# BaromBoard.net
KiCad netlist of a schematic drawn in EAGLE
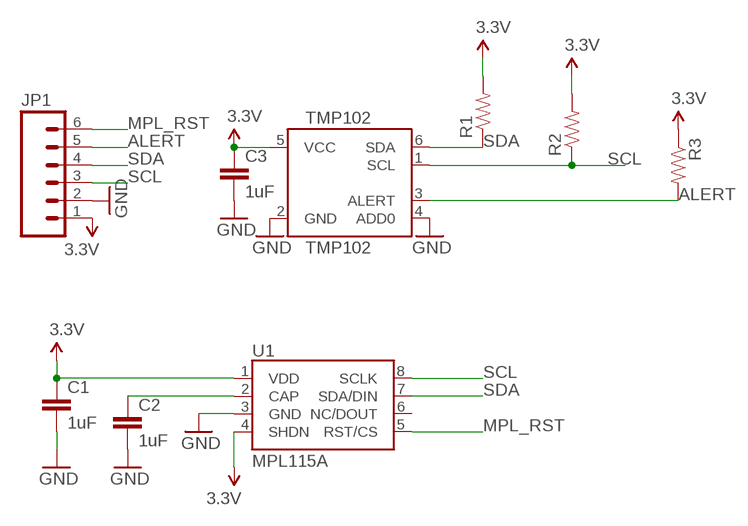
[diagram p0: schematic, sheet 1]

(export (version "E")
  (design (tool "Eeschema 10.0.6"))
  (components
    (comp (ref "C1")
      (value "1uF")
      (footprint "eagle-import:0603-CAP")
      (libsource (lib "eagle-import") (part "CAP0603-CAP"))
    )
    (comp (ref "C2")
      (value "1uF")
      (footprint "eagle-import:0603-CAP")
      (libsource (lib "eagle-import") (part "CAP0603-CAP"))
    )
    (comp (ref "C3")
      (value "1uF")
      (footprint "eagle-import:0603-CAP")
      (libsource (lib "eagle-import") (part "CAP0603-CAP"))
    )
    (comp (ref "JP1")
      (value "M06SIP")
      (footprint "eagle-import:1X06")
      (libsource (lib "eagle-import") (part "M06SIP"))
    )
    (comp (ref "R1")
      (value "RESISTOR0603-RES")
      (footprint "eagle-import:0603-RES")
      (libsource (lib "eagle-import") (part "RESISTOR0603-RES"))
    )
    (comp (ref "R2")
      (value "RESISTOR0603-RES")
      (footprint "eagle-import:0603-RES")
      (libsource (lib "eagle-import") (part "RESISTOR0603-RES"))
    )
    (comp (ref "R3")
      (value "RESISTOR0603-RES")
      (footprint "eagle-import:0603-RES")
      (libsource (lib "eagle-import") (part "RESISTOR0603-RES"))
    )
    (comp (ref "TMP102")
      (value "TMP102")
      (footprint "eagle-import:SOT563")
      (libsource (lib "eagle-import") (part "TMP102"))
    )
    (comp (ref "U1")
      (value "MPL115A")
      (footprint "eagle-import:LGA8")
      (libsource (lib "eagle-import") (part "MPL115A"))
    )
  )
  (nets
    (net (code "1") (name "/ALERT") (class "Default")
      (node (ref "JP1") (pin "5") (pinfunction "5_5") (pintype "passive"))
      (node (ref "R3") (pin "2") (pinfunction "2_2") (pintype "passive"))
      (node (ref "TMP102") (pin "3") (pinfunction "ALERT_3") (pintype "bidirectional"))
    )
    (net (code "2") (name "/MPL_RST") (class "Default")
      (node (ref "JP1") (pin "6") (pinfunction "6_6") (pintype "passive"))
      (node (ref "U1") (pin "5") (pinfunction "RST/CS_5") (pintype "bidirectional"))
    )
    (net (code "3") (name "/SCL") (class "Default")
      (node (ref "JP1") (pin "3") (pinfunction "3_3") (pintype "passive"))
      (node (ref "R2") (pin "1") (pinfunction "1_1") (pintype "passive"))
      (node (ref "TMP102") (pin "1") (pinfunction "SCL_1") (pintype "bidirectional"))
      (node (ref "U1") (pin "8") (pinfunction "SCLK_8") (pintype "bidirectional"))
    )
    (net (code "4") (name "/SDA") (class "Default")
      (node (ref "JP1") (pin "4") (pinfunction "4_4") (pintype "passive"))
      (node (ref "R1") (pin "1") (pinfunction "1_1") (pintype "passive"))
      (node (ref "TMP102") (pin "6") (pinfunction "SDA_6") (pintype "bidirectional"))
      (node (ref "U1") (pin "7") (pinfunction "SDA/DIN_7") (pintype "bidirectional"))
    )
    (net (code "5") (name "3.3V") (class "Default")
      (node (ref "C1") (pin "1") (pinfunction "1_1") (pintype "passive"))
      (node (ref "C3") (pin "1") (pinfunction "1_1") (pintype "passive"))
      (node (ref "JP1") (pin "1") (pinfunction "1_1") (pintype "passive"))
      (node (ref "R1") (pin "2") (pinfunction "2_2") (pintype "passive"))
      (node (ref "R2") (pin "2") (pinfunction "2_2") (pintype "passive"))
      (node (ref "R3") (pin "1") (pinfunction "1_1") (pintype "passive"))
      (node (ref "TMP102") (pin "5") (pinfunction "VCC_5") (pintype "bidirectional"))
      (node (ref "U1") (pin "1") (pinfunction "VDD_1") (pintype "bidirectional"))
      (node (ref "U1") (pin "4") (pinfunction "SHDN_4") (pintype "bidirectional"))
    )
    (net (code "6") (name "GND") (class "Default")
      (node (ref "C1") (pin "2") (pinfunction "2_2") (pintype "passive"))
      (node (ref "C2") (pin "2") (pinfunction "2_2") (pintype "passive"))
      (node (ref "C3") (pin "2") (pinfunction "2_2") (pintype "passive"))
      (node (ref "JP1") (pin "2") (pinfunction "2_2") (pintype "passive"))
      (node (ref "TMP102") (pin "2") (pinfunction "GND_2") (pintype "bidirectional"))
      (node (ref "TMP102") (pin "4") (pinfunction "ADD0_4") (pintype "bidirectional"))
      (node (ref "U1") (pin "3") (pinfunction "GND_3") (pintype "bidirectional"))
    )
    (net (code "7") (name "Net-(U1-CAP)") (class "Default")
      (node (ref "C2") (pin "1") (pinfunction "1_1") (pintype "passive"))
      (node (ref "U1") (pin "2") (pinfunction "CAP_2") (pintype "bidirectional"))
    )
    (net (code "8") (name "unconnected-(U1-NC{slash}DOUT-Pad6)") (class "Default")
      (node (ref "U1") (pin "6") (pinfunction "NC/DOUT_6") (pintype "bidirectional"))
    )
  )
)
